# UBTB_original.net
KiCad netlist of a schematic drawn in EAGLE
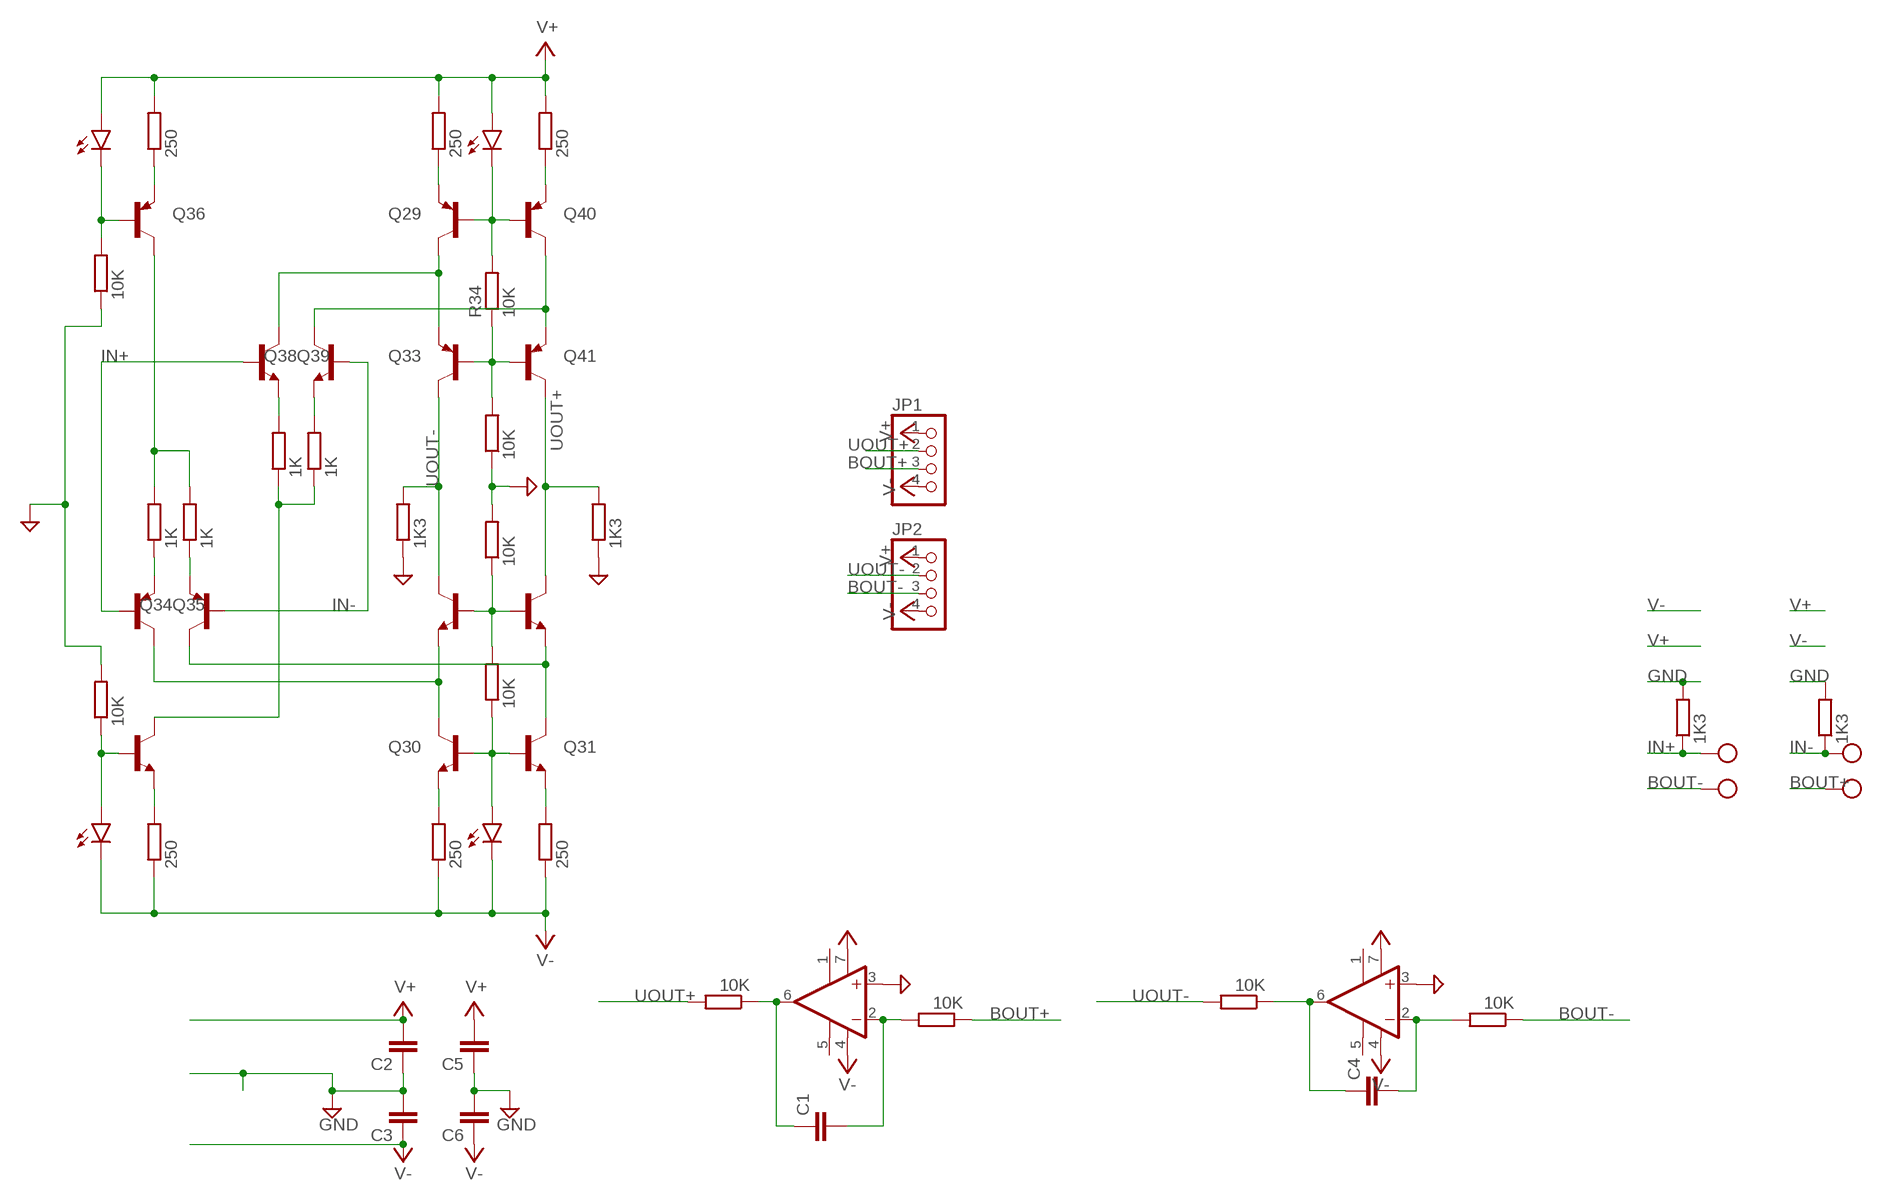
[diagram p0: schematic, sheet 1]

(export (version "E")
  (design (tool "Eeschema 10.0.6"))
  (components
    (comp (ref "C1")
      (value "C-EUC1206")
      (footprint "eagle-import:C1206")
      (libsource (lib "eagle-import") (part "C-EUC1206"))
    )
    (comp (ref "C2")
      (value "C-EUC0805")
      (footprint "eagle-import:C0805")
      (libsource (lib "eagle-import") (part "C-EUC0805"))
    )
    (comp (ref "C3")
      (value "C-EUC0805")
      (footprint "eagle-import:C0805")
      (libsource (lib "eagle-import") (part "C-EUC0805"))
    )
    (comp (ref "C4")
      (value "C-EUC1206")
      (footprint "eagle-import:C1206")
      (libsource (lib "eagle-import") (part "C-EUC1206"))
    )
    (comp (ref "C5")
      (value "C-EUC0805")
      (footprint "eagle-import:C0805")
      (libsource (lib "eagle-import") (part "C-EUC0805"))
    )
    (comp (ref "C6")
      (value "C-EUC0805")
      (footprint "eagle-import:C0805")
      (libsource (lib "eagle-import") (part "C-EUC0805"))
    )
    (comp (ref "IC1")
      (value "OPA627U")
      (footprint "eagle-import:SO08")
      (fields (field (name "MF") "TEXAS INSTRUMENTS") (field (name "MPN") "OPA627AU"))
      (libsource (lib "eagle-import") (part "OPA627U"))
    )
    (comp (ref "IC2")
      (value "OPA627U")
      (footprint "eagle-import:SO08")
      (fields (field (name "MF") "TEXAS INSTRUMENTS") (field (name "MPN") "OPA627AU"))
      (libsource (lib "eagle-import") (part "OPA627U"))
    )
    (comp (ref "JP1")
      (value "PINHD-1X4")
      (footprint "eagle-import:1X04")
      (libsource (lib "eagle-import") (part "PINHD-1X4"))
    )
    (comp (ref "JP2")
      (value "PINHD-1X4")
      (footprint "eagle-import:1X04")
      (libsource (lib "eagle-import") (part "PINHD-1X4"))
    )
    (comp (ref "LED1")
      (value "LEDCHIPLED_1206")
      (footprint "eagle-import:CHIPLED_1206")
      (libsource (lib "eagle-import") (part "LEDCHIPLED_1206"))
    )
    (comp (ref "LED2")
      (value "LEDCHIPLED_1206")
      (footprint "eagle-import:CHIPLED_1206")
      (libsource (lib "eagle-import") (part "LEDCHIPLED_1206"))
    )
    (comp (ref "LED3")
      (value "LEDCHIPLED_1206")
      (footprint "eagle-import:CHIPLED_1206")
      (libsource (lib "eagle-import") (part "LEDCHIPLED_1206"))
    )
    (comp (ref "LED4")
      (value "LEDCHIPLED_1206")
      (footprint "eagle-import:CHIPLED_1206")
      (fields (field (name "SPICEPREFIX") "D"))
      (libsource (lib "eagle-import") (part "LEDCHIPLED_1206"))
    )
    (comp (ref "Q26")
      (value "BC847CSMD")
      (footprint "eagle-import:SOT23")
      (fields (field (name "SPICEPREFIX") "Q"))
      (libsource (lib "eagle-import") (part "BC847SMDC"))
    )
    (comp (ref "Q29")
      (value "BC857CSMD")
      (footprint "eagle-import:SOT23-BEC")
      (fields (field (name "SPICEPREFIX") "Q"))
      (libsource (lib "eagle-import") (part "BC857SMDC"))
    )
    (comp (ref "Q30")
      (value "BC847CSMD")
      (footprint "eagle-import:SOT23")
      (fields (field (name "SPICEPREFIX") "Q"))
      (libsource (lib "eagle-import") (part "BC847SMDC"))
    )
    (comp (ref "Q31")
      (value "BC847CSMD")
      (footprint "eagle-import:SOT23")
      (fields (field (name "SPICEPREFIX") "Q"))
      (libsource (lib "eagle-import") (part "BC847SMDC"))
    )
    (comp (ref "Q32")
      (value "BC847CSMD")
      (footprint "eagle-import:SOT23")
      (fields (field (name "SPICEPREFIX") "Q"))
      (libsource (lib "eagle-import") (part "BC847SMDC"))
    )
    (comp (ref "Q33")
      (value "BC857CSMD")
      (footprint "eagle-import:SOT23-BEC")
      (fields (field (name "SPICEPREFIX") "Q"))
      (libsource (lib "eagle-import") (part "BC857SMDC"))
    )
    (comp (ref "Q34")
      (value "BC857CSMD")
      (footprint "eagle-import:SOT23-BEC")
      (fields (field (name "SPICEPREFIX") "Q"))
      (libsource (lib "eagle-import") (part "BC857SMDC"))
    )
    (comp (ref "Q35")
      (value "BC857CSMD")
      (footprint "eagle-import:SOT23-BEC")
      (fields (field (name "SPICEPREFIX") "Q"))
      (libsource (lib "eagle-import") (part "BC857SMDC"))
    )
    (comp (ref "Q36")
      (value "BC857CSMD")
      (footprint "eagle-import:SOT23-BEC")
      (fields (field (name "SPICEPREFIX") "Q"))
      (libsource (lib "eagle-import") (part "BC857SMDC"))
    )
    (comp (ref "Q37")
      (value "BC847CSMD")
      (footprint "eagle-import:SOT23")
      (fields (field (name "SPICEPREFIX") "Q"))
      (libsource (lib "eagle-import") (part "BC847SMDC"))
    )
    (comp (ref "Q38")
      (value "BC847CSMD")
      (footprint "eagle-import:SOT23")
      (fields (field (name "SPICEPREFIX") "Q"))
      (libsource (lib "eagle-import") (part "BC847SMDC"))
    )
    (comp (ref "Q39")
      (value "BC847CSMD")
      (footprint "eagle-import:SOT23")
      (fields (field (name "SPICEPREFIX") "Q"))
      (libsource (lib "eagle-import") (part "BC847SMDC"))
    )
    (comp (ref "Q40")
      (value "BC857CSMD")
      (footprint "eagle-import:SOT23-BEC")
      (fields (field (name "SPICEPREFIX") "Q"))
      (libsource (lib "eagle-import") (part "BC857SMDC"))
    )
    (comp (ref "Q41")
      (value "BC857CSMD")
      (footprint "eagle-import:SOT23-BEC")
      (fields (field (name "SPICEPREFIX") "Q"))
      (libsource (lib "eagle-import") (part "BC857SMDC"))
    )
    (comp (ref "R1")
      (value "1K3")
      (footprint "eagle-import:MINI_MELF-0204W")
      (libsource (lib "eagle-import") (part "R-EU_MELF0204W"))
    )
    (comp (ref "R2")
      (value "1K3")
      (footprint "eagle-import:MINI_MELF-0204W")
      (libsource (lib "eagle-import") (part "R-EU_MELF0204W"))
    )
    (comp (ref "R16")
      (value "10K")
      (footprint "eagle-import:MINI_MELF-0204W")
      (libsource (lib "eagle-import") (part "R-EU_MELF0204W"))
    )
    (comp (ref "R17")
      (value "10K")
      (footprint "eagle-import:MINI_MELF-0204W")
      (libsource (lib "eagle-import") (part "R-EU_MELF0204W"))
    )
    (comp (ref "R22")
      (value "250")
      (footprint "eagle-import:MINI_MELF-0204W")
      (libsource (lib "eagle-import") (part "R-EU_MELF0204W"))
    )
    (comp (ref "R23")
      (value "250")
      (footprint "eagle-import:MINI_MELF-0204W")
      (libsource (lib "eagle-import") (part "R-EU_MELF0204W"))
    )
    (comp (ref "R29")
      (value "10K")
      (footprint "eagle-import:MINI_MELF-0204W")
      (libsource (lib "eagle-import") (part "R-EU_MELF0204W"))
    )
    (comp (ref "R32")
      (value "10K")
      (footprint "eagle-import:MINI_MELF-0204W")
      (libsource (lib "eagle-import") (part "R-EU_MELF0204W"))
    )
    (comp (ref "R33")
      (value "10K")
      (footprint "eagle-import:MINI_MELF-0204W")
      (libsource (lib "eagle-import") (part "R-EU_MELF0204W"))
    )
    (comp (ref "R34")
      (value "10K")
      (footprint "eagle-import:MINI_MELF-0204W")
      (libsource (lib "eagle-import") (part "R-EU_MELF0204W"))
    )
    (comp (ref "R35")
      (value "250")
      (footprint "eagle-import:MINI_MELF-0204W")
      (libsource (lib "eagle-import") (part "R-EU_MELF0204W"))
    )
    (comp (ref "R36")
      (value "250")
      (footprint "eagle-import:MINI_MELF-0204W")
      (libsource (lib "eagle-import") (part "R-EU_MELF0204W"))
    )
    (comp (ref "R37")
      (value "1K3")
      (footprint "eagle-import:MINI_MELF-0204W")
      (libsource (lib "eagle-import") (part "R-EU_MELF0204W"))
    )
    (comp (ref "R38")
      (value "1K3")
      (footprint "eagle-import:MINI_MELF-0204W")
      (libsource (lib "eagle-import") (part "R-EU_MELF0204W"))
    )
    (comp (ref "R39")
      (value "1K")
      (footprint "eagle-import:MINI_MELF-0204W")
      (libsource (lib "eagle-import") (part "R-EU_MELF0204W"))
    )
    (comp (ref "R40")
      (value "1K")
      (footprint "eagle-import:MINI_MELF-0204W")
      (libsource (lib "eagle-import") (part "R-EU_MELF0204W"))
    )
    (comp (ref "R41")
      (value "1K")
      (footprint "eagle-import:MINI_MELF-0204W")
      (libsource (lib "eagle-import") (part "R-EU_MELF0204W"))
    )
    (comp (ref "R42")
      (value "1K")
      (footprint "eagle-import:MINI_MELF-0204W")
      (libsource (lib "eagle-import") (part "R-EU_MELF0204W"))
    )
    (comp (ref "R43")
      (value "250")
      (footprint "eagle-import:MINI_MELF-0204W")
      (libsource (lib "eagle-import") (part "R-EU_MELF0204W"))
    )
    (comp (ref "R44")
      (value "250")
      (footprint "eagle-import:MINI_MELF-0204W")
      (fields (field (name "SPICEPREFIX") "R"))
      (libsource (lib "eagle-import") (part "R-EU_MELF0204W"))
    )
    (comp (ref "R45")
      (value "10K")
      (footprint "eagle-import:MINI_MELF-0204W")
      (libsource (lib "eagle-import") (part "R-EU_MELF0204W"))
    )
    (comp (ref "R46")
      (value "10K")
      (footprint "eagle-import:MINI_MELF-0204W")
      (libsource (lib "eagle-import") (part "R-EU_MELF0204W"))
    )
    (comp (ref "R48")
      (value "10K")
      (footprint "eagle-import:MINI_MELF-0204W")
      (libsource (lib "eagle-import") (part "R-EU_MELF0204W"))
    )
    (comp (ref "R51")
      (value "10K")
      (footprint "eagle-import:MINI_MELF-0204W")
      (libsource (lib "eagle-import") (part "R-EU_MELF0204W"))
    )
    (comp (ref "X3")
      (value "CON-PHOENIX-508_MKDSN1,5/2-5,08")
      (footprint "eagle-import:CON-PHOENIX-508_MKDSN1,5_2-5,08")
      (libsource (lib "eagle-import") (part "CON-PHOENIX-508_MKDSN1,5/2-5,08"))
    )
    (comp (ref "X4")
      (value "CON-PHOENIX-508_MKDSN1,5/2-5,08")
      (footprint "eagle-import:CON-PHOENIX-508_MKDSN1,5_2-5,08")
      (libsource (lib "eagle-import") (part "CON-PHOENIX-508_MKDSN1,5/2-5,08"))
    )
  )
  (nets
    (net (code "1") (name "/BOUT+") (class "Default")
      (node (ref "JP1") (pin "3") (pinfunction "3_3") (pintype "passive"))
      (node (ref "R17") (pin "1") (pinfunction "1_1") (pintype "passive"))
      (node (ref "X4") (pin "2") (pinfunction "KL_2") (pintype "passive"))
    )
    (net (code "2") (name "/BOUT-") (class "Default")
      (node (ref "JP2") (pin "3") (pinfunction "3_3") (pintype "passive"))
      (node (ref "R48") (pin "1") (pinfunction "1_1") (pintype "passive"))
      (node (ref "X3") (pin "2") (pinfunction "KL_2") (pintype "passive"))
    )
    (net (code "3") (name "/IN+") (class "Default")
      (node (ref "Q35") (pin "B") (pinfunction "B_B") (pintype "passive"))
      (node (ref "Q39") (pin "1") (pinfunction "B_1") (pintype "passive"))
      (node (ref "R1") (pin "1") (pinfunction "1_1") (pintype "passive"))
      (node (ref "X3") (pin "1") (pinfunction "KL_1") (pintype "passive"))
    )
    (net (code "4") (name "/IN-") (class "Default")
      (node (ref "Q34") (pin "B") (pinfunction "B_B") (pintype "passive"))
      (node (ref "Q38") (pin "1") (pinfunction "B_1") (pintype "passive"))
      (node (ref "R2") (pin "1") (pinfunction "1_1") (pintype "passive"))
      (node (ref "X4") (pin "1") (pinfunction "KL_1") (pintype "passive"))
    )
    (net (code "5") (name "/UOUT+") (class "Default")
      (node (ref "JP1") (pin "2") (pinfunction "2_2") (pintype "passive"))
      (node (ref "Q32") (pin "3") (pinfunction "C_3") (pintype "passive"))
      (node (ref "Q41") (pin "C") (pinfunction "C_C") (pintype "passive"))
      (node (ref "R16") (pin "2") (pinfunction "2_2") (pintype "passive"))
      (node (ref "R38") (pin "2") (pinfunction "2_2") (pintype "passive"))
    )
    (net (code "6") (name "/UOUT-") (class "Default")
      (node (ref "JP2") (pin "2") (pinfunction "2_2") (pintype "passive"))
      (node (ref "Q33") (pin "C") (pinfunction "C_C") (pintype "passive"))
      (node (ref "Q37") (pin "3") (pinfunction "C_3") (pintype "passive"))
      (node (ref "R37") (pin "2") (pinfunction "2_2") (pintype "passive"))
      (node (ref "R51") (pin "2") (pinfunction "2_2") (pintype "passive"))
    )
    (net (code "7") (name "GND") (class "Default")
      (node (ref "C2") (pin "1") (pinfunction "1_1") (pintype "passive"))
      (node (ref "C3") (pin "2") (pinfunction "2_2") (pintype "passive"))
      (node (ref "C5") (pin "1") (pinfunction "1_1") (pintype "passive"))
      (node (ref "C6") (pin "2") (pinfunction "2_2") (pintype "passive"))
      (node (ref "IC1") (pin "3") (pinfunction "+IN_3") (pintype "input"))
      (node (ref "IC2") (pin "3") (pinfunction "+IN_3") (pintype "input"))
      (node (ref "R1") (pin "2") (pinfunction "2_2") (pintype "passive"))
      (node (ref "R2") (pin "2") (pinfunction "2_2") (pintype "passive"))
      (node (ref "R32") (pin "2") (pinfunction "2_2") (pintype "passive"))
      (node (ref "R33") (pin "1") (pinfunction "1_1") (pintype "passive"))
      (node (ref "R37") (pin "1") (pinfunction "1_1") (pintype "passive"))
      (node (ref "R38") (pin "1") (pinfunction "1_1") (pintype "passive"))
      (node (ref "R45") (pin "1") (pinfunction "1_1") (pintype "passive"))
      (node (ref "R46") (pin "2") (pinfunction "2_2") (pintype "passive"))
    )
    (net (code "8") (name "Net-(IC1--IN)") (class "Default")
      (node (ref "C1") (pin "2") (pinfunction "2_2") (pintype "passive"))
      (node (ref "IC1") (pin "2") (pinfunction "-IN_2") (pintype "input"))
      (node (ref "R17") (pin "2") (pinfunction "2_2") (pintype "passive"))
    )
    (net (code "9") (name "Net-(IC1-OUT)") (class "Default")
      (node (ref "C1") (pin "1") (pinfunction "1_1") (pintype "passive"))
      (node (ref "IC1") (pin "6") (pinfunction "OUT_6") (pintype "output"))
      (node (ref "R16") (pin "1") (pinfunction "1_1") (pintype "passive"))
    )
    (net (code "10") (name "Net-(IC2--IN)") (class "Default")
      (node (ref "C4") (pin "2") (pinfunction "2_2") (pintype "passive"))
      (node (ref "IC2") (pin "2") (pinfunction "-IN_2") (pintype "input"))
      (node (ref "R48") (pin "2") (pinfunction "2_2") (pintype "passive"))
    )
    (net (code "11") (name "Net-(IC2-OUT)") (class "Default")
      (node (ref "C4") (pin "1") (pinfunction "1_1") (pintype "passive"))
      (node (ref "IC2") (pin "6") (pinfunction "OUT_6") (pintype "output"))
      (node (ref "R51") (pin "1") (pinfunction "1_1") (pintype "passive"))
    )
    (net (code "12") (name "Net-(LED2-PadC)") (class "Default")
      (node (ref "LED2") (pin "C") (pinfunction "C_C") (pintype "passive"))
      (node (ref "Q29") (pin "B") (pinfunction "B_B") (pintype "passive"))
      (node (ref "Q40") (pin "B") (pinfunction "B_B") (pintype "passive"))
      (node (ref "R34") (pin "2") (pinfunction "2_2") (pintype "passive"))
    )
    (net (code "13") (name "Net-(LED3-PadC)") (class "Default")
      (node (ref "LED3") (pin "C") (pinfunction "C_C") (pintype "passive"))
      (node (ref "Q36") (pin "B") (pinfunction "B_B") (pintype "passive"))
      (node (ref "R45") (pin "2") (pinfunction "2_2") (pintype "passive"))
    )
    (net (code "14") (name "Net-(Q26-B)") (class "Default")
      (node (ref "LED4") (pin "A") (pinfunction "A_A") (pintype "passive"))
      (node (ref "Q26") (pin "1") (pinfunction "B_1") (pintype "passive"))
      (node (ref "R46") (pin "1") (pinfunction "1_1") (pintype "passive"))
    )
    (net (code "15") (name "Net-(Q26-C)") (class "Default")
      (node (ref "Q26") (pin "3") (pinfunction "C_3") (pintype "passive"))
      (node (ref "R39") (pin "1") (pinfunction "1_1") (pintype "passive"))
      (node (ref "R40") (pin "1") (pinfunction "1_1") (pintype "passive"))
    )
    (net (code "16") (name "Net-(Q26-E)") (class "Default")
      (node (ref "Q26") (pin "2") (pinfunction "E_2") (pintype "passive"))
      (node (ref "R44") (pin "2") (pinfunction "2_2") (pintype "passive"))
    )
    (net (code "17") (name "Net-(Q29-PadE)") (class "Default")
      (node (ref "Q29") (pin "E") (pinfunction "E_E") (pintype "passive"))
      (node (ref "R35") (pin "1") (pinfunction "1_1") (pintype "passive"))
    )
    (net (code "18") (name "Net-(Q30-B)") (class "Default")
      (node (ref "LED1") (pin "A") (pinfunction "A_A") (pintype "passive"))
      (node (ref "Q30") (pin "1") (pinfunction "B_1") (pintype "passive"))
      (node (ref "Q31") (pin "1") (pinfunction "B_1") (pintype "passive"))
      (node (ref "R29") (pin "1") (pinfunction "1_1") (pintype "passive"))
    )
    (net (code "19") (name "Net-(Q30-C)") (class "Default")
      (node (ref "Q30") (pin "3") (pinfunction "C_3") (pintype "passive"))
      (node (ref "Q35") (pin "C") (pinfunction "C_C") (pintype "passive"))
      (node (ref "Q37") (pin "2") (pinfunction "E_2") (pintype "passive"))
    )
    (net (code "20") (name "Net-(Q30-E)") (class "Default")
      (node (ref "Q30") (pin "2") (pinfunction "E_2") (pintype "passive"))
      (node (ref "R22") (pin "2") (pinfunction "2_2") (pintype "passive"))
    )
    (net (code "21") (name "Net-(Q31-C)") (class "Default")
      (node (ref "Q31") (pin "3") (pinfunction "C_3") (pintype "passive"))
      (node (ref "Q32") (pin "2") (pinfunction "E_2") (pintype "passive"))
      (node (ref "Q34") (pin "C") (pinfunction "C_C") (pintype "passive"))
    )
    (net (code "22") (name "Net-(Q31-E)") (class "Default")
      (node (ref "Q31") (pin "2") (pinfunction "E_2") (pintype "passive"))
      (node (ref "R23") (pin "2") (pinfunction "2_2") (pintype "passive"))
    )
    (net (code "23") (name "Net-(Q32-B)") (class "Default")
      (node (ref "Q32") (pin "1") (pinfunction "B_1") (pintype "passive"))
      (node (ref "Q37") (pin "1") (pinfunction "B_1") (pintype "passive"))
      (node (ref "R29") (pin "2") (pinfunction "2_2") (pintype "passive"))
      (node (ref "R32") (pin "1") (pinfunction "1_1") (pintype "passive"))
    )
    (net (code "24") (name "Net-(Q33-PadB)") (class "Default")
      (node (ref "Q33") (pin "B") (pinfunction "B_B") (pintype "passive"))
      (node (ref "Q41") (pin "B") (pinfunction "B_B") (pintype "passive"))
      (node (ref "R33") (pin "2") (pinfunction "2_2") (pintype "passive"))
      (node (ref "R34") (pin "1") (pinfunction "1_1") (pintype "passive"))
    )
    (net (code "25") (name "Net-(Q34-PadE)") (class "Default")
      (node (ref "Q34") (pin "E") (pinfunction "E_E") (pintype "passive"))
      (node (ref "R42") (pin "1") (pinfunction "1_1") (pintype "passive"))
    )
    (net (code "26") (name "Net-(Q35-PadE)") (class "Default")
      (node (ref "Q35") (pin "E") (pinfunction "E_E") (pintype "passive"))
      (node (ref "R41") (pin "1") (pinfunction "1_1") (pintype "passive"))
    )
    (net (code "27") (name "Net-(Q36-PadC)") (class "Default")
      (node (ref "Q36") (pin "C") (pinfunction "C_C") (pintype "passive"))
      (node (ref "R41") (pin "2") (pinfunction "2_2") (pintype "passive"))
      (node (ref "R42") (pin "2") (pinfunction "2_2") (pintype "passive"))
    )
    (net (code "28") (name "Net-(Q36-PadE)") (class "Default")
      (node (ref "Q36") (pin "E") (pinfunction "E_E") (pintype "passive"))
      (node (ref "R43") (pin "1") (pinfunction "1_1") (pintype "passive"))
    )
    (net (code "29") (name "Net-(Q38-C)") (class "Default")
      (node (ref "Q38") (pin "3") (pinfunction "C_3") (pintype "passive"))
      (node (ref "Q40") (pin "C") (pinfunction "C_C") (pintype "passive"))
      (node (ref "Q41") (pin "E") (pinfunction "E_E") (pintype "passive"))
    )
    (net (code "30") (name "Net-(Q38-E)") (class "Default")
      (node (ref "Q38") (pin "2") (pinfunction "E_2") (pintype "passive"))
      (node (ref "R40") (pin "2") (pinfunction "2_2") (pintype "passive"))
    )
    (net (code "31") (name "Net-(Q39-C)") (class "Default")
      (node (ref "Q29") (pin "C") (pinfunction "C_C") (pintype "passive"))
      (node (ref "Q33") (pin "E") (pinfunction "E_E") (pintype "passive"))
      (node (ref "Q39") (pin "3") (pinfunction "C_3") (pintype "passive"))
    )
    (net (code "32") (name "Net-(Q39-E)") (class "Default")
      (node (ref "Q39") (pin "2") (pinfunction "E_2") (pintype "passive"))
      (node (ref "R39") (pin "2") (pinfunction "2_2") (pintype "passive"))
    )
    (net (code "33") (name "Net-(Q40-PadE)") (class "Default")
      (node (ref "Q40") (pin "E") (pinfunction "E_E") (pintype "passive"))
      (node (ref "R36") (pin "1") (pinfunction "1_1") (pintype "passive"))
    )
    (net (code "34") (name "V+") (class "Default")
      (node (ref "C2") (pin "2") (pinfunction "2_2") (pintype "passive"))
      (node (ref "C5") (pin "2") (pinfunction "2_2") (pintype "passive"))
      (node (ref "IC1") (pin "7") (pinfunction "V+_7") (pintype "power_in"))
      (node (ref "IC2") (pin "7") (pinfunction "V+_7") (pintype "power_in"))
      (node (ref "JP1") (pin "1") (pinfunction "1_1") (pintype "passive"))
      (node (ref "JP2") (pin "1") (pinfunction "1_1") (pintype "passive"))
      (node (ref "LED2") (pin "A") (pinfunction "A_A") (pintype "passive"))
      (node (ref "LED3") (pin "A") (pinfunction "A_A") (pintype "passive"))
      (node (ref "R35") (pin "2") (pinfunction "2_2") (pintype "passive"))
      (node (ref "R36") (pin "2") (pinfunction "2_2") (pintype "passive"))
      (node (ref "R43") (pin "2") (pinfunction "2_2") (pintype "passive"))
    )
    (net (code "35") (name "V-") (class "Default")
      (node (ref "C3") (pin "1") (pinfunction "1_1") (pintype "passive"))
      (node (ref "C6") (pin "1") (pinfunction "1_1") (pintype "passive"))
      (node (ref "IC1") (pin "4") (pinfunction "V-_4") (pintype "power_in"))
      (node (ref "IC2") (pin "4") (pinfunction "V-_4") (pintype "power_in"))
      (node (ref "JP1") (pin "4") (pinfunction "4_4") (pintype "passive"))
      (node (ref "JP2") (pin "4") (pinfunction "4_4") (pintype "passive"))
      (node (ref "LED1") (pin "C") (pinfunction "C_C") (pintype "passive"))
      (node (ref "LED4") (pin "C") (pinfunction "C_C") (pintype "passive"))
      (node (ref "R22") (pin "1") (pinfunction "1_1") (pintype "passive"))
      (node (ref "R23") (pin "1") (pinfunction "1_1") (pintype "passive"))
      (node (ref "R44") (pin "1") (pinfunction "1_1") (pintype "passive"))
    )
    (net (code "36") (name "unconnected-(IC1-TRIM1-Pad1)") (class "Default")
      (node (ref "IC1") (pin "1") (pinfunction "TRIM1_1") (pintype "passive"))
    )
    (net (code "37") (name "unconnected-(IC1-TRIM2-Pad5)") (class "Default")
      (node (ref "IC1") (pin "5") (pinfunction "TRIM2_5") (pintype "passive"))
    )
    (net (code "38") (name "unconnected-(IC2-TRIM1-Pad1)") (class "Default")
      (node (ref "IC2") (pin "1") (pinfunction "TRIM1_1") (pintype "passive"))
    )
    (net (code "39") (name "unconnected-(IC2-TRIM2-Pad5)") (class "Default")
      (node (ref "IC2") (pin "5") (pinfunction "TRIM2_5") (pintype "passive"))
    )
  )
)
